# Controller_V0_1.net
KiCad netlist of a schematic drawn in EAGLE
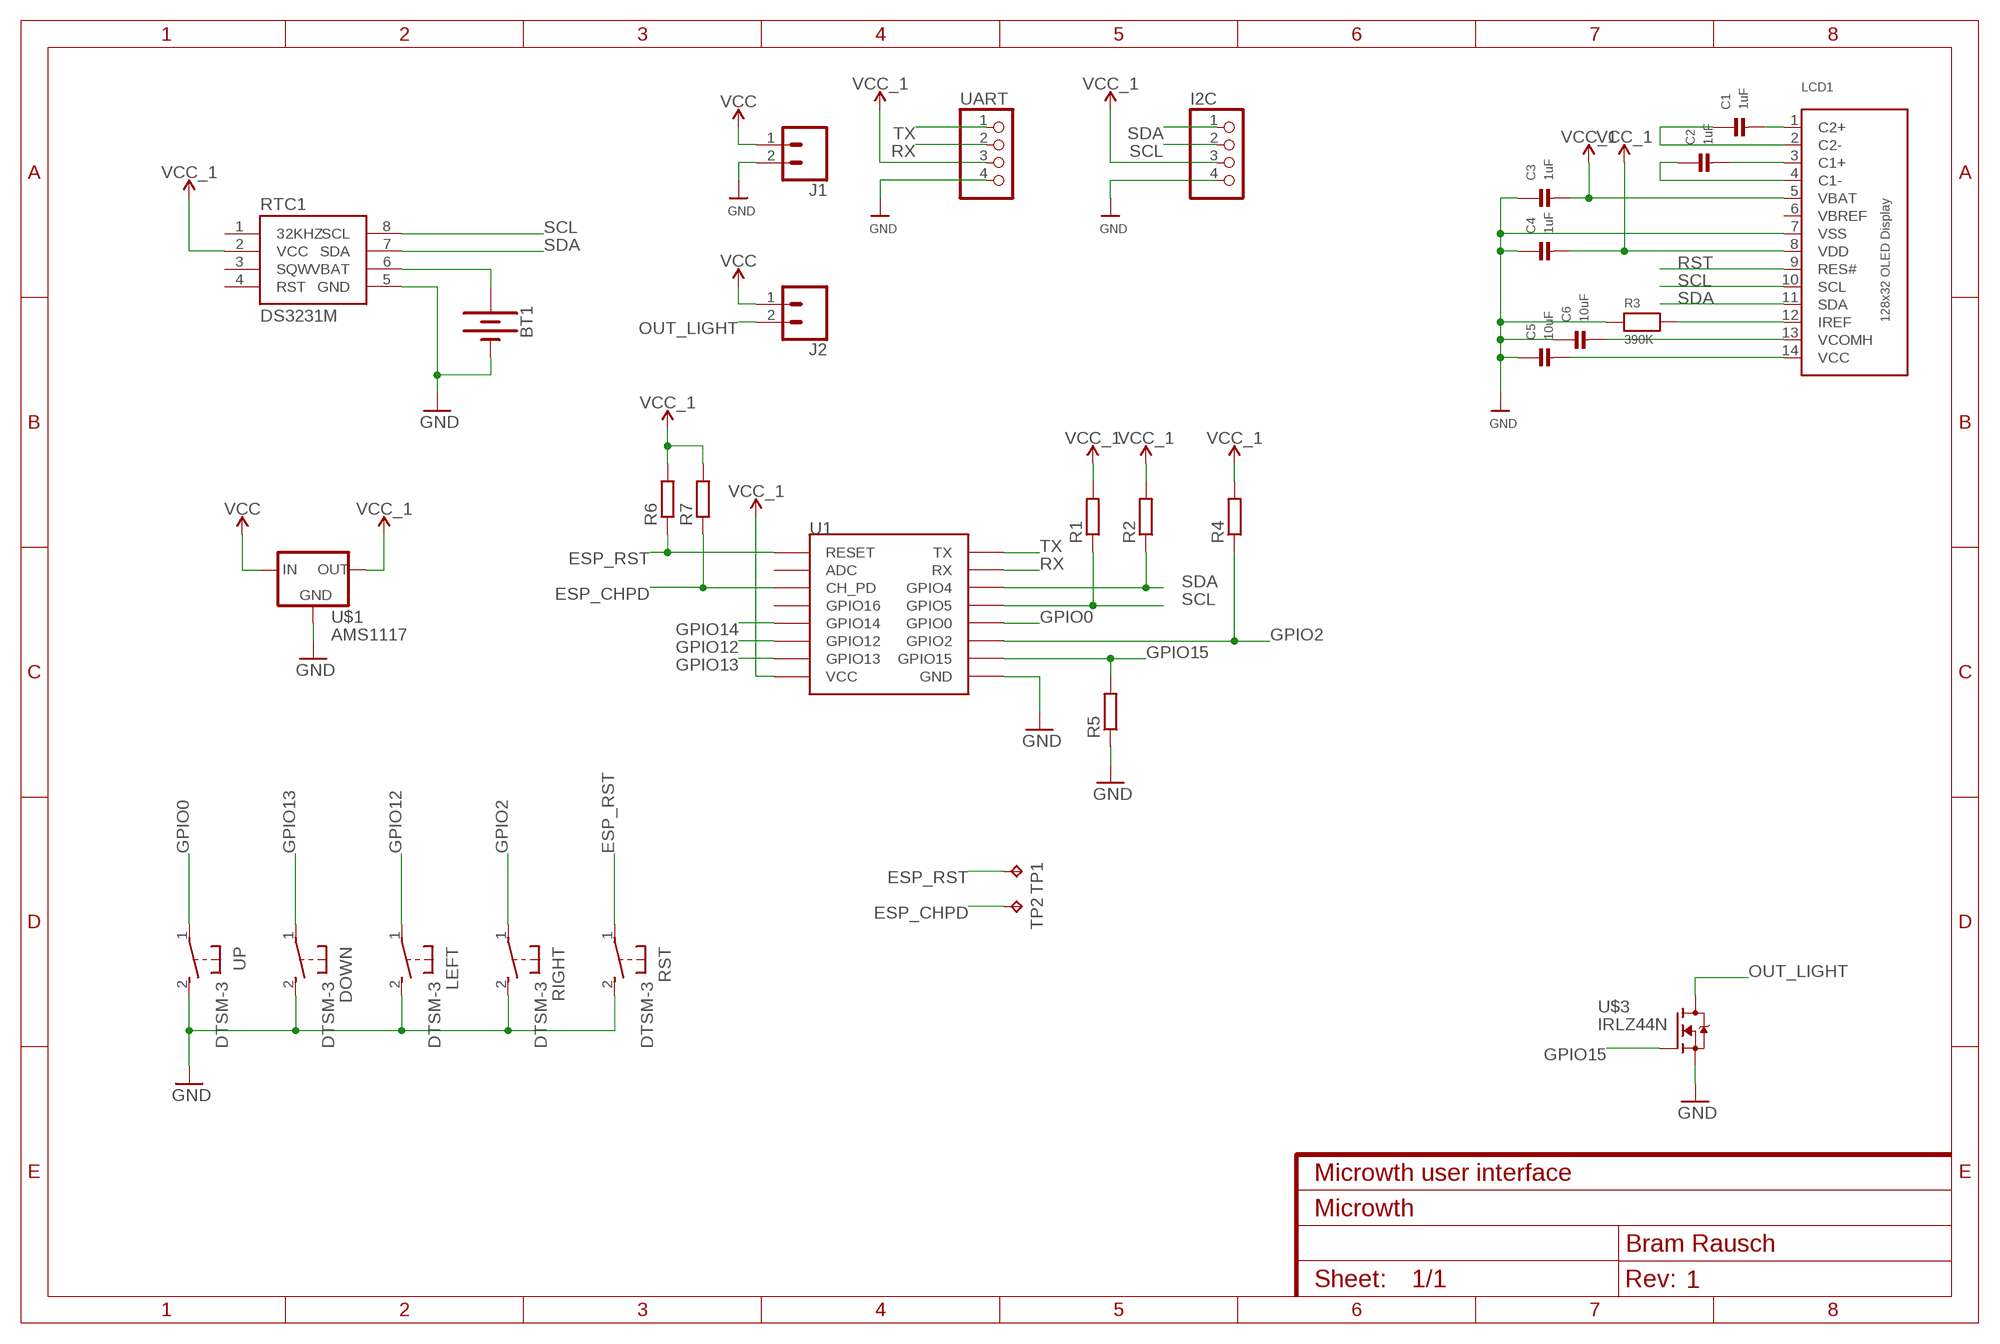
[diagram p0: schematic, sheet 1]

(export (version "E")
  (design (tool "Eeschema 10.0.6"))
  (components
    (comp (ref "BT1")
      (value "BATTERY-20MM_PTH")
      (footprint "eagle-import:BATTCOM_20MM_PTH")
      (libsource (lib "eagle-import") (part "BATTERY-20MM_PTH"))
    )
    (comp (ref "C1")
      (value "1uF")
      (footprint "eagle-import:0805")
      (libsource (lib "eagle-import") (part "CAP_CERAMIC0805"))
    )
    (comp (ref "C2")
      (value "1uF")
      (footprint "eagle-import:0805")
      (libsource (lib "eagle-import") (part "CAP_CERAMIC0805"))
    )
    (comp (ref "C3")
      (value "1uF")
      (footprint "eagle-import:0805")
      (libsource (lib "eagle-import") (part "CAP_CERAMIC0805"))
    )
    (comp (ref "C4")
      (value "1uF")
      (footprint "eagle-import:0805")
      (libsource (lib "eagle-import") (part "CAP_CERAMIC0805"))
    )
    (comp (ref "C5")
      (value "10uF")
      (footprint "eagle-import:0805")
      (libsource (lib "eagle-import") (part "CAP_CERAMIC0805"))
    )
    (comp (ref "C6")
      (value "10uF")
      (footprint "eagle-import:0805")
      (libsource (lib "eagle-import") (part "CAP_CERAMIC0805"))
    )
    (comp (ref "DOWN")
      (value "DTSM-3")
      (footprint "eagle-import:DTSM-3")
      (libsource (lib "eagle-import") (part "DTSM-3"))
    )
    (comp (ref "I2C")
      (value "PINHD-1X4")
      (footprint "eagle-import:1X04")
      (libsource (lib "eagle-import") (part "PINHD-1X4"))
    )
    (comp (ref "J1")
      (value "CONN_02PTH4")
      (footprint "eagle-import:1X02_XTRA_BIG")
      (libsource (lib "eagle-import") (part "CONN_02PTH4"))
    )
    (comp (ref "J2")
      (value "CONN_02PTH4")
      (footprint "eagle-import:1X02_XTRA_BIG")
      (libsource (lib "eagle-import") (part "CONN_02PTH4"))
    )
    (comp (ref "LCD1")
      (value "DISP_OLED_UG-2832HSWEG02")
      (footprint "eagle-import:UG-2832HSWEG02_WRAPUNDER")
      (libsource (lib "eagle-import") (part "DISP_OLED_UG-2832HSWEG02"))
    )
    (comp (ref "LEFT")
      (value "DTSM-3")
      (footprint "eagle-import:DTSM-3")
      (libsource (lib "eagle-import") (part "DTSM-3"))
    )
    (comp (ref "R1")
      (value "R-EU_R0805")
      (footprint "eagle-import:R0805")
      (libsource (lib "eagle-import") (part "R-EU_R0805"))
    )
    (comp (ref "R2")
      (value "R-EU_R0805")
      (footprint "eagle-import:R0805")
      (libsource (lib "eagle-import") (part "R-EU_R0805"))
    )
    (comp (ref "R3")
      (value "390K")
      (footprint "eagle-import:0805")
      (libsource (lib "eagle-import") (part "RESISTOR0805"))
    )
    (comp (ref "R4")
      (value "R-EU_R0805")
      (footprint "eagle-import:R0805")
      (libsource (lib "eagle-import") (part "R-EU_R0805"))
    )
    (comp (ref "R5")
      (value "R-EU_R0805")
      (footprint "eagle-import:R0805")
      (libsource (lib "eagle-import") (part "R-EU_R0805"))
    )
    (comp (ref "R6")
      (value "R-EU_R0805")
      (footprint "eagle-import:R0805")
      (libsource (lib "eagle-import") (part "R-EU_R0805"))
    )
    (comp (ref "R7")
      (value "R-EU_R0805")
      (footprint "eagle-import:R0805")
      (libsource (lib "eagle-import") (part "R-EU_R0805"))
    )
    (comp (ref "RIGHT")
      (value "DTSM-3")
      (footprint "eagle-import:DTSM-3")
      (libsource (lib "eagle-import") (part "DTSM-3"))
    )
    (comp (ref "RST")
      (value "DTSM-3")
      (footprint "eagle-import:DTSM-3")
      (libsource (lib "eagle-import") (part "DTSM-3"))
    )
    (comp (ref "RTC1")
      (value "DS3231M")
      (footprint "eagle-import:SO08")
      (libsource (lib "eagle-import") (part "DS3231M"))
    )
    (comp (ref "TP1")
      (value "TPB2,54")
      (footprint "eagle-import:B2,54")
      (libsource (lib "eagle-import") (part "TPB2,54"))
    )
    (comp (ref "TP2")
      (value "TPB2,54")
      (footprint "eagle-import:B2,54")
      (libsource (lib "eagle-import") (part "TPB2,54"))
    )
    (comp (ref "U$1")
      (value "AMS1117")
      (footprint "eagle-import:SOT223")
      (libsource (lib "eagle-import") (part "AMS1117"))
    )
    (comp (ref "U$3")
      (value "IRLZ44N")
      (footprint "eagle-import:TO220")
      (libsource (lib "eagle-import") (part "IRLZ44N"))
    )
    (comp (ref "U1")
      (value "ESP12SMD")
      (footprint "eagle-import:ESP12-SMD")
      (libsource (lib "eagle-import") (part "ESP12SMD"))
    )
    (comp (ref "UART")
      (value "PINHD-1X4")
      (footprint "eagle-import:1X04")
      (libsource (lib "eagle-import") (part "PINHD-1X4"))
    )
    (comp (ref "UP")
      (value "DTSM-3")
      (footprint "eagle-import:DTSM-3")
      (libsource (lib "eagle-import") (part "DTSM-3"))
    )
  )
  (nets
    (net (code "1") (name "/ESP_CHPD") (class "Default")
      (node (ref "R7") (pin "1") (pinfunction "1_1") (pintype "passive"))
      (node (ref "TP2") (pin "TP") (pinfunction "TP_TP") (pintype "input"))
      (node (ref "U1") (pin "CH_PD") (pinfunction "CH_PD_CH_PD") (pintype "bidirectional"))
    )
    (net (code "2") (name "/ESP_RST") (class "Default")
      (node (ref "R6") (pin "1") (pinfunction "1_1") (pintype "passive"))
      (node (ref "RST") (pin "1") (pinfunction "1_1") (pintype "passive"))
      (node (ref "TP1") (pin "TP") (pinfunction "TP_TP") (pintype "input"))
      (node (ref "U1") (pin "RESET") (pinfunction "RESET_RESET") (pintype "bidirectional"))
    )
    (net (code "3") (name "/GPIO0") (class "Default")
      (node (ref "U1") (pin "GPIO0") (pinfunction "GPIO0_GPIO0") (pintype "bidirectional"))
      (node (ref "UP") (pin "1") (pinfunction "1_1") (pintype "passive"))
    )
    (net (code "4") (name "/GPIO2") (class "Default")
      (node (ref "R4") (pin "1") (pinfunction "1_1") (pintype "passive"))
      (node (ref "RIGHT") (pin "1") (pinfunction "1_1") (pintype "passive"))
      (node (ref "U1") (pin "GPIO2") (pinfunction "GPIO2_GPIO2") (pintype "bidirectional"))
    )
    (net (code "5") (name "/GPIO12") (class "Default")
      (node (ref "LEFT") (pin "1") (pinfunction "1_1") (pintype "passive"))
      (node (ref "U1") (pin "GPIO12") (pinfunction "GPIO12_GPIO12") (pintype "bidirectional"))
    )
    (net (code "6") (name "/GPIO13") (class "Default")
      (node (ref "DOWN") (pin "1") (pinfunction "1_1") (pintype "passive"))
      (node (ref "U1") (pin "GPIO13") (pinfunction "GPIO13_GPIO13") (pintype "bidirectional"))
    )
    (net (code "7") (name "/GPIO14") (class "Default")
      (node (ref "U1") (pin "GPIO14") (pinfunction "GPIO14_GPIO14") (pintype "bidirectional"))
    )
    (net (code "8") (name "/GPIO15") (class "Default")
      (node (ref "R5") (pin "2") (pinfunction "2_2") (pintype "passive"))
      (node (ref "U$3") (pin "1") (pinfunction "G_1") (pintype "passive"))
      (node (ref "U1") (pin "GPIO15") (pinfunction "GPIO15_GPIO15") (pintype "bidirectional"))
    )
    (net (code "9") (name "/OUT_LIGHT") (class "Default")
      (node (ref "J2") (pin "2") (pinfunction "2_2") (pintype "passive"))
      (node (ref "U$3") (pin "2") (pinfunction "D_2") (pintype "passive"))
    )
    (net (code "10") (name "/RST") (class "Default")
      (node (ref "LCD1") (pin "9") (pinfunction "RES#_9") (pintype "bidirectional"))
    )
    (net (code "11") (name "/RX") (class "Default")
      (node (ref "U1") (pin "RXD0") (pinfunction "RX_RXD0") (pintype "bidirectional"))
      (node (ref "UART") (pin "2") (pinfunction "2_2") (pintype "passive"))
    )
    (net (code "12") (name "/SCL") (class "Default")
      (node (ref "I2C") (pin "2") (pinfunction "2_2") (pintype "passive"))
      (node (ref "LCD1") (pin "10") (pinfunction "SCL_10") (pintype "bidirectional"))
      (node (ref "R1") (pin "1") (pinfunction "1_1") (pintype "passive"))
      (node (ref "RTC1") (pin "8") (pinfunction "SCL_8") (pintype "bidirectional"))
      (node (ref "U1") (pin "GPIO5") (pinfunction "GPIO5_GPIO5") (pintype "bidirectional"))
    )
    (net (code "13") (name "/SDA") (class "Default")
      (node (ref "I2C") (pin "1") (pinfunction "1_1") (pintype "passive"))
      (node (ref "LCD1") (pin "11") (pinfunction "SDA_11") (pintype "bidirectional"))
      (node (ref "R2") (pin "1") (pinfunction "1_1") (pintype "passive"))
      (node (ref "RTC1") (pin "7") (pinfunction "SDA_7") (pintype "bidirectional"))
      (node (ref "U1") (pin "GPIO4") (pinfunction "GPIO4_GPIO4") (pintype "bidirectional"))
    )
    (net (code "14") (name "/TX") (class "Default")
      (node (ref "U1") (pin "TXD0") (pinfunction "TX_TXD0") (pintype "bidirectional"))
      (node (ref "UART") (pin "1") (pinfunction "1_1") (pintype "passive"))
    )
    (net (code "15") (name "/VBREF") (class "Default")
      (node (ref "LCD1") (pin "6") (pinfunction "VBREF_6") (pintype "power_in"))
    )
    (net (code "16") (name "GND") (class "Default")
      (node (ref "BT1") (pin "2") (pinfunction "-_2") (pintype "power_in"))
      (node (ref "C3") (pin "1") (pinfunction "P$1_1") (pintype "passive"))
      (node (ref "C4") (pin "1") (pinfunction "P$1_1") (pintype "passive"))
      (node (ref "C5") (pin "1") (pinfunction "P$1_1") (pintype "passive"))
      (node (ref "C6") (pin "1") (pinfunction "P$1_1") (pintype "passive"))
      (node (ref "DOWN") (pin "2") (pinfunction "2_2") (pintype "passive"))
      (node (ref "I2C") (pin "4") (pinfunction "4_4") (pintype "passive"))
      (node (ref "J1") (pin "2") (pinfunction "2_2") (pintype "passive"))
      (node (ref "LCD1") (pin "7") (pinfunction "VSS_7") (pintype "power_in"))
      (node (ref "LEFT") (pin "2") (pinfunction "2_2") (pintype "passive"))
      (node (ref "R3") (pin "1") (pinfunction "1_1") (pintype "passive"))
      (node (ref "R5") (pin "1") (pinfunction "1_1") (pintype "passive"))
      (node (ref "RIGHT") (pin "2") (pinfunction "2_2") (pintype "passive"))
      (node (ref "RST") (pin "2") (pinfunction "2_2") (pintype "passive"))
      (node (ref "RTC1") (pin "5") (pinfunction "GND_5") (pintype "power_in"))
      (node (ref "U$1") (pin "1") (pinfunction "GND_1") (pintype "input"))
      (node (ref "U$3") (pin "3") (pinfunction "S_3") (pintype "passive"))
      (node (ref "U1") (pin "GND") (pinfunction "GND_GND") (pintype "bidirectional"))
      (node (ref "UART") (pin "4") (pinfunction "4_4") (pintype "passive"))
      (node (ref "UP") (pin "2") (pinfunction "2_2") (pintype "passive"))
    )
    (net (code "17") (name "Net-(BT1-+)") (class "Default")
      (node (ref "BT1") (pin "1") (pinfunction "+_1") (pintype "power_in"))
      (node (ref "RTC1") (pin "6") (pinfunction "VBAT_6") (pintype "power_in"))
    )
    (net (code "18") (name "Net-(C1-P$1)") (class "Default")
      (node (ref "C1") (pin "1") (pinfunction "P$1_1") (pintype "passive"))
      (node (ref "LCD1") (pin "2") (pinfunction "C2-_2") (pintype "bidirectional"))
    )
    (net (code "19") (name "Net-(C1-P$2)") (class "Default")
      (node (ref "C1") (pin "2") (pinfunction "P$2_2") (pintype "passive"))
      (node (ref "LCD1") (pin "1") (pinfunction "C2+_1") (pintype "bidirectional"))
    )
    (net (code "20") (name "Net-(C2-P$1)") (class "Default")
      (node (ref "C2") (pin "1") (pinfunction "P$1_1") (pintype "passive"))
      (node (ref "LCD1") (pin "4") (pinfunction "C1-_4") (pintype "bidirectional"))
    )
    (net (code "21") (name "Net-(C2-P$2)") (class "Default")
      (node (ref "C2") (pin "2") (pinfunction "P$2_2") (pintype "passive"))
      (node (ref "LCD1") (pin "3") (pinfunction "C1+_3") (pintype "bidirectional"))
    )
    (net (code "22") (name "Net-(C5-P$2)") (class "Default")
      (node (ref "C5") (pin "2") (pinfunction "P$2_2") (pintype "passive"))
      (node (ref "LCD1") (pin "14") (pinfunction "VCC_14") (pintype "power_in"))
    )
    (net (code "23") (name "Net-(C6-P$2)") (class "Default")
      (node (ref "C6") (pin "2") (pinfunction "P$2_2") (pintype "passive"))
      (node (ref "LCD1") (pin "13") (pinfunction "VCOMH_13") (pintype "power_in"))
    )
    (net (code "24") (name "Net-(LCD1-IREF)") (class "Default")
      (node (ref "LCD1") (pin "12") (pinfunction "IREF_12") (pintype "bidirectional"))
      (node (ref "R3") (pin "2") (pinfunction "2_2") (pintype "passive"))
    )
    (net (code "25") (name "VCC") (class "Default")
      (node (ref "J1") (pin "1") (pinfunction "1_1") (pintype "passive"))
      (node (ref "J2") (pin "1") (pinfunction "1_1") (pintype "passive"))
      (node (ref "U$1") (pin "3") (pinfunction "IN_3") (pintype "input"))
    )
    (net (code "26") (name "VCC_1") (class "Default")
      (node (ref "C3") (pin "2") (pinfunction "P$2_2") (pintype "passive"))
      (node (ref "C4") (pin "2") (pinfunction "P$2_2") (pintype "passive"))
      (node (ref "I2C") (pin "3") (pinfunction "3_3") (pintype "passive"))
      (node (ref "LCD1") (pin "5") (pinfunction "VBAT_5") (pintype "power_in"))
      (node (ref "LCD1") (pin "8") (pinfunction "VDD_8") (pintype "power_in"))
      (node (ref "R1") (pin "2") (pinfunction "2_2") (pintype "passive"))
      (node (ref "R2") (pin "2") (pinfunction "2_2") (pintype "passive"))
      (node (ref "R4") (pin "2") (pinfunction "2_2") (pintype "passive"))
      (node (ref "R6") (pin "2") (pinfunction "2_2") (pintype "passive"))
      (node (ref "R7") (pin "2") (pinfunction "2_2") (pintype "passive"))
      (node (ref "RTC1") (pin "2") (pinfunction "VCC_2") (pintype "power_in"))
      (node (ref "U$1") (pin "2") (pinfunction "OUT_2") (pintype "passive"))
      (node (ref "U1") (pin "VCC") (pinfunction "VCC_VCC") (pintype "bidirectional"))
      (node (ref "UART") (pin "3") (pinfunction "3_3") (pintype "passive"))
    )
    (net (code "27") (name "unconnected-(RTC1-32KHZ-Pad1)") (class "Default")
      (node (ref "RTC1") (pin "1") (pinfunction "32KHZ_1") (pintype "output"))
    )
    (net (code "28") (name "unconnected-(RTC1-RST-Pad4)") (class "Default")
      (node (ref "RTC1") (pin "4") (pinfunction "RST_4") (pintype "bidirectional"))
    )
    (net (code "29") (name "unconnected-(RTC1-SQW-Pad3)") (class "Default")
      (node (ref "RTC1") (pin "3") (pinfunction "SQW_3") (pintype "output"))
    )
    (net (code "30") (name "unconnected-(U1-PadADC)") (class "Default")
      (node (ref "U1") (pin "ADC") (pinfunction "ADC_ADC") (pintype "bidirectional"))
    )
    (net (code "31") (name "unconnected-(U1-PadGPIO16)") (class "Default")
      (node (ref "U1") (pin "GPIO16") (pinfunction "GPIO16_GPIO16") (pintype "bidirectional"))
    )
  )
)
